# Sheet_1_2022-06-01.net
KiCad netlist of a schematic drawn in Altium Designer
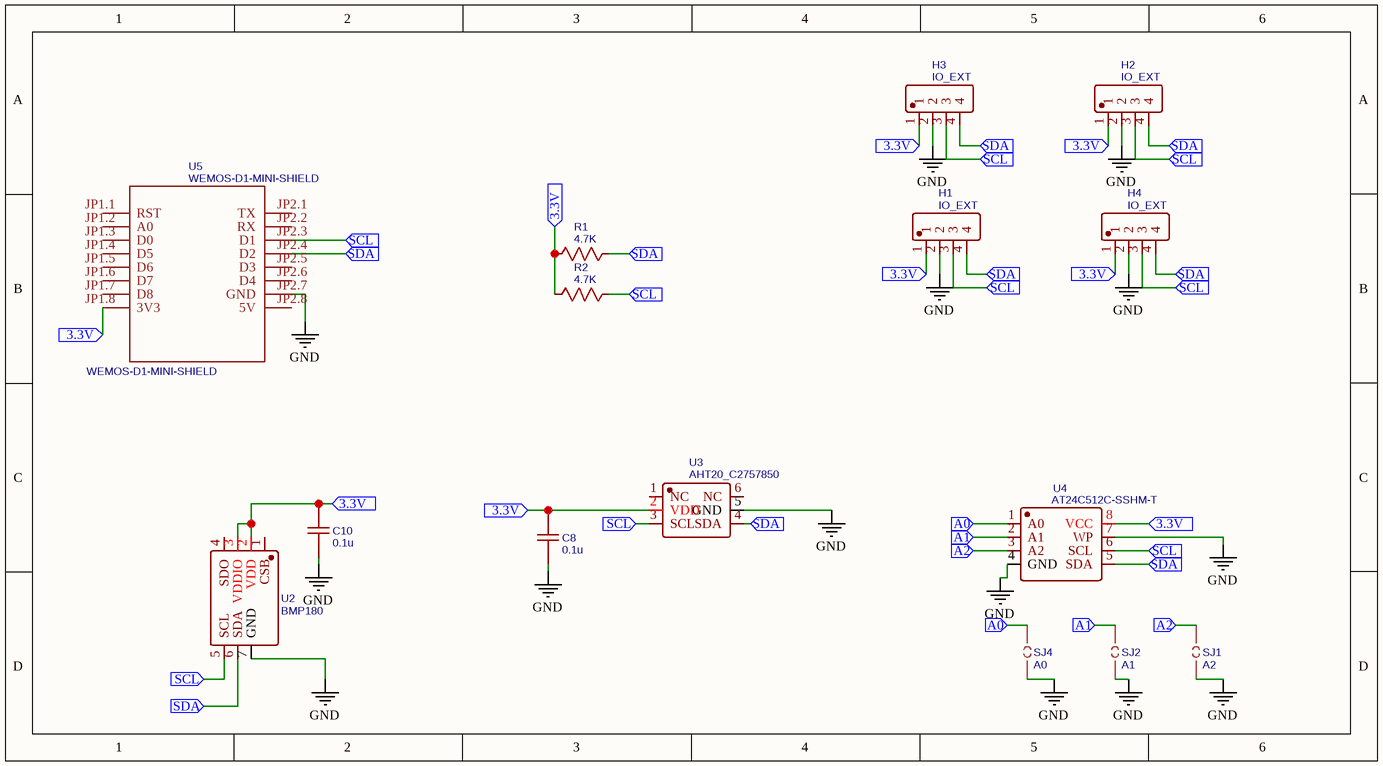
[diagram p0: Sheet_1_2022-06-01.schdoc]

(export (version "E")
  (design (tool "Eeschema 10.0.6"))
  (components
    (comp (ref "C8")
      (value "0.1u")
      (fields (field (name "CONTRIBUTOR") "LCEDA_Lib"))
      (libsource (lib "altium-import") (part "root_1_0.1u_"))
    )
    (comp (ref "C10")
      (value "0.1u")
      (fields (field (name "CONTRIBUTOR") "LCEDA_Lib"))
      (libsource (lib "altium-import") (part "root_1_0.1u_"))
    )
    (comp (ref "H1")
      (value "IO_EXT")
      (fields
        (field (name "BOM_SUPPLIER PART") "C706876")
        (field (name "BOM_MANUFACTURER PART") "X6511WV-04H-C30D60")
        (field (name "CONTRIBUTOR") "LCSC")
      )
      (libsource (lib "altium-import") (part "root_1_IO_EXT_"))
    )
    (comp (ref "H2")
      (value "IO_EXT")
      (fields
        (field (name "BOM_SUPPLIER PART") "C706876")
        (field (name "BOM_MANUFACTURER PART") "X6511WV-04H-C30D60")
        (field (name "CONTRIBUTOR") "LCSC")
      )
      (libsource (lib "altium-import") (part "root_1_IO_EXT_"))
    )
    (comp (ref "H3")
      (value "IO_EXT")
      (fields
        (field (name "BOM_SUPPLIER PART") "C706876")
        (field (name "BOM_MANUFACTURER PART") "X6511WV-04H-C30D60")
        (field (name "CONTRIBUTOR") "LCSC")
      )
      (libsource (lib "altium-import") (part "root_1_IO_EXT_"))
    )
    (comp (ref "H4")
      (value "IO_EXT")
      (fields
        (field (name "BOM_SUPPLIER PART") "C706876")
        (field (name "BOM_MANUFACTURER PART") "X6511WV-04H-C30D60")
        (field (name "CONTRIBUTOR") "LCSC")
      )
      (libsource (lib "altium-import") (part "root_1_IO_EXT_"))
    )
    (comp (ref "R1")
      (value "4.7K")
      (fields (field (name "CONTRIBUTOR") "LCEDA_Lib"))
      (libsource (lib "altium-import") (part "root_2_4.7K_"))
    )
    (comp (ref "R2")
      (value "4.7K")
      (fields (field (name "CONTRIBUTOR") "LCEDA_Lib"))
      (libsource (lib "altium-import") (part "root_2_4.7K_"))
    )
    (comp (ref "SJ1")
      (value "A2")
      (fields (field (name "CONTRIBUTOR") "torusww"))
      (libsource (lib "altium-import") (part "root_1_A2_"))
    )
    (comp (ref "SJ2")
      (value "A1")
      (fields (field (name "CONTRIBUTOR") "torusww"))
      (libsource (lib "altium-import") (part "root_1_A1_"))
    )
    (comp (ref "SJ4")
      (value "A0")
      (fields (field (name "CONTRIBUTOR") "torusww"))
      (libsource (lib "altium-import") (part "root_1_A0_"))
    )
    (comp (ref "U2")
      (value "BMP180")
      (fields (field (name "BOM_SUPPLIER PART") "C438474") (field (name "CONTRIBUTOR") "LCSC"))
      (libsource (lib "altium-import") (part "root_3_BMP180_"))
    )
    (comp (ref "U3")
      (value "AHT20_C2757850")
      (fields
        (field (name "BOM_SUPPLIER PART") "C2757850")
        (field (name "BOM_MANUFACTURER PART") "AHT20")
        (field (name "CONTRIBUTOR") "LCSC")
      )
      (libsource (lib "altium-import") (part "root_0_AHT20_C2757850_"))
    )
    (comp (ref "U4")
      (value "AT24C512C-SSHM-T")
      (fields (field (name "BOM_SUPPLIER PART") "C54668"))
      (libsource (lib "altium-import") (part "root_0_AT24C512C-SSHM-T_"))
    )
    (comp (ref "U5")
      (value "WEMOS-D1-MINI-SHIELD")
      (description "Template for WEMOS D1 mini compatible shields")
      (libsource (lib "altium-import") (part "root_0_WEMOS-D1-MINI-SHIELD_"))
    )
  )
  (nets
    (net (code "1") (name "/3.3V") (class "Default")
      (node (ref "C10") (pin "2") (pinfunction "2_2") (pintype "passive"))
      (node (ref "C8") (pin "2") (pinfunction "2_2") (pintype "passive"))
      (node (ref "H1") (pin "1") (pinfunction "1_1") (pintype "passive"))
      (node (ref "H2") (pin "1") (pinfunction "1_1") (pintype "passive"))
      (node (ref "H3") (pin "1") (pinfunction "1_1") (pintype "passive"))
      (node (ref "H4") (pin "1") (pinfunction "1_1") (pintype "passive"))
      (node (ref "R1") (pin "2") (pinfunction "2_2") (pintype "passive"))
      (node (ref "R2") (pin "2") (pinfunction "2_2") (pintype "passive"))
      (node (ref "U2") (pin "2") (pinfunction "VDD_2") (pintype "passive"))
      (node (ref "U2") (pin "3") (pinfunction "VDDIO_3") (pintype "passive"))
      (node (ref "U3") (pin "2") (pinfunction "VDD_2") (pintype "passive"))
      (node (ref "U4") (pin "8") (pinfunction "VCC_8") (pintype "passive"))
      (node (ref "U5") (pin "JP1.8") (pinfunction "3V3_JP1.8") (pintype "passive"))
    )
    (net (code "2") (name "/A0") (class "Default")
      (node (ref "SJ4") (pin "2") (pinfunction "2_2") (pintype "passive"))
      (node (ref "U4") (pin "1") (pinfunction "A0_1") (pintype "passive"))
    )
    (net (code "3") (name "/A1") (class "Default")
      (node (ref "SJ2") (pin "2") (pinfunction "2_2") (pintype "passive"))
      (node (ref "U4") (pin "2") (pinfunction "A1_2") (pintype "passive"))
    )
    (net (code "4") (name "/A2") (class "Default")
      (node (ref "SJ1") (pin "2") (pinfunction "2_2") (pintype "passive"))
      (node (ref "U4") (pin "3") (pinfunction "A2_3") (pintype "passive"))
    )
    (net (code "5") (name "/SCL") (class "Default")
      (node (ref "H1") (pin "3") (pinfunction "3_3") (pintype "passive"))
      (node (ref "H2") (pin "3") (pinfunction "3_3") (pintype "passive"))
      (node (ref "H3") (pin "3") (pinfunction "3_3") (pintype "passive"))
      (node (ref "H4") (pin "3") (pinfunction "3_3") (pintype "passive"))
      (node (ref "R2") (pin "1") (pinfunction "1_1") (pintype "passive"))
      (node (ref "U2") (pin "5") (pinfunction "SCL_5") (pintype "passive"))
      (node (ref "U3") (pin "3") (pinfunction "SCL_3") (pintype "passive"))
      (node (ref "U4") (pin "6") (pinfunction "SCL_6") (pintype "passive"))
      (node (ref "U5") (pin "JP2.3") (pinfunction "D1_JP2.3") (pintype "passive"))
    )
    (net (code "6") (name "/SDA") (class "Default")
      (node (ref "H1") (pin "4") (pinfunction "4_4") (pintype "passive"))
      (node (ref "H2") (pin "4") (pinfunction "4_4") (pintype "passive"))
      (node (ref "H3") (pin "4") (pinfunction "4_4") (pintype "passive"))
      (node (ref "H4") (pin "4") (pinfunction "4_4") (pintype "passive"))
      (node (ref "R1") (pin "1") (pinfunction "1_1") (pintype "passive"))
      (node (ref "U2") (pin "6") (pinfunction "SDA_6") (pintype "passive"))
      (node (ref "U3") (pin "4") (pinfunction "SDA_4") (pintype "passive"))
      (node (ref "U4") (pin "5") (pinfunction "SDA_5") (pintype "passive"))
      (node (ref "U5") (pin "JP2.4") (pinfunction "D2_JP2.4") (pintype "passive"))
    )
    (net (code "7") (name "GND") (class "Default")
      (node (ref "C10") (pin "1") (pinfunction "1_1") (pintype "passive"))
      (node (ref "C8") (pin "1") (pinfunction "1_1") (pintype "passive"))
      (node (ref "H1") (pin "2") (pinfunction "2_2") (pintype "passive"))
      (node (ref "H2") (pin "2") (pinfunction "2_2") (pintype "passive"))
      (node (ref "H3") (pin "2") (pinfunction "2_2") (pintype "passive"))
      (node (ref "H4") (pin "2") (pinfunction "2_2") (pintype "passive"))
      (node (ref "SJ1") (pin "1") (pinfunction "1_1") (pintype "passive"))
      (node (ref "SJ2") (pin "1") (pinfunction "1_1") (pintype "passive"))
      (node (ref "SJ4") (pin "1") (pinfunction "1_1") (pintype "passive"))
      (node (ref "U2") (pin "7") (pinfunction "GND_7") (pintype "passive"))
      (node (ref "U3") (pin "5") (pinfunction "GND_5") (pintype "passive"))
      (node (ref "U4") (pin "4") (pinfunction "GND_4") (pintype "passive"))
      (node (ref "U4") (pin "7") (pinfunction "WP_7") (pintype "passive"))
      (node (ref "U5") (pin "JP2.7") (pinfunction "GND_JP2.7") (pintype "passive"))
    )
    (net (code "8") (name "unconnected-(U2-CSB-Pad1)") (class "Default")
      (node (ref "U2") (pin "1") (pinfunction "CSB_1") (pintype "passive"))
    )
    (net (code "9") (name "unconnected-(U2-SDO-Pad4)") (class "Default")
      (node (ref "U2") (pin "4") (pinfunction "SDO_4") (pintype "passive"))
    )
    (net (code "10") (name "unconnected-(U3-NC-Pad1)") (class "Default")
      (node (ref "U3") (pin "1") (pinfunction "NC_1") (pintype "passive"))
    )
    (net (code "11") (name "unconnected-(U3-NC-Pad6)") (class "Default")
      (node (ref "U3") (pin "6") (pinfunction "NC_6") (pintype "passive"))
    )
    (net (code "12") (name "unconnected-(U5-5V-PadJP2.8)") (class "Default")
      (node (ref "U5") (pin "JP2.8") (pinfunction "5V_JP2.8") (pintype "passive"))
    )
    (net (code "13") (name "unconnected-(U5-A0-PadJP1.2)") (class "Default")
      (node (ref "U5") (pin "JP1.2") (pinfunction "A0_JP1.2") (pintype "passive"))
    )
    (net (code "14") (name "unconnected-(U5-D0-PadJP1.3)") (class "Default")
      (node (ref "U5") (pin "JP1.3") (pinfunction "D0_JP1.3") (pintype "passive"))
    )
    (net (code "15") (name "unconnected-(U5-D3-PadJP2.5)") (class "Default")
      (node (ref "U5") (pin "JP2.5") (pinfunction "D3_JP2.5") (pintype "passive"))
    )
    (net (code "16") (name "unconnected-(U5-D4-PadJP2.6)") (class "Default")
      (node (ref "U5") (pin "JP2.6") (pinfunction "D4_JP2.6") (pintype "passive"))
    )
    (net (code "17") (name "unconnected-(U5-D5-PadJP1.4)") (class "Default")
      (node (ref "U5") (pin "JP1.4") (pinfunction "D5_JP1.4") (pintype "passive"))
    )
    (net (code "18") (name "unconnected-(U5-D6-PadJP1.5)") (class "Default")
      (node (ref "U5") (pin "JP1.5") (pinfunction "D6_JP1.5") (pintype "passive"))
    )
    (net (code "19") (name "unconnected-(U5-D7-PadJP1.6)") (class "Default")
      (node (ref "U5") (pin "JP1.6") (pinfunction "D7_JP1.6") (pintype "passive"))
    )
    (net (code "20") (name "unconnected-(U5-D8-PadJP1.7)") (class "Default")
      (node (ref "U5") (pin "JP1.7") (pinfunction "D8_JP1.7") (pintype "passive"))
    )
    (net (code "21") (name "unconnected-(U5-RST-PadJP1.1)") (class "Default")
      (node (ref "U5") (pin "JP1.1") (pinfunction "RST_JP1.1") (pintype "passive"))
    )
    (net (code "22") (name "unconnected-(U5-RX-PadJP2.2)") (class "Default")
      (node (ref "U5") (pin "JP2.2") (pinfunction "RX_JP2.2") (pintype "passive"))
    )
    (net (code "23") (name "unconnected-(U5-TX-PadJP2.1)") (class "Default")
      (node (ref "U5") (pin "JP2.1") (pinfunction "TX_JP2.1") (pintype "passive"))
    )
  )
)
